# 16_Inputs_Card_schematic.net
KiCad netlist of a schematic drawn in EasyEDA
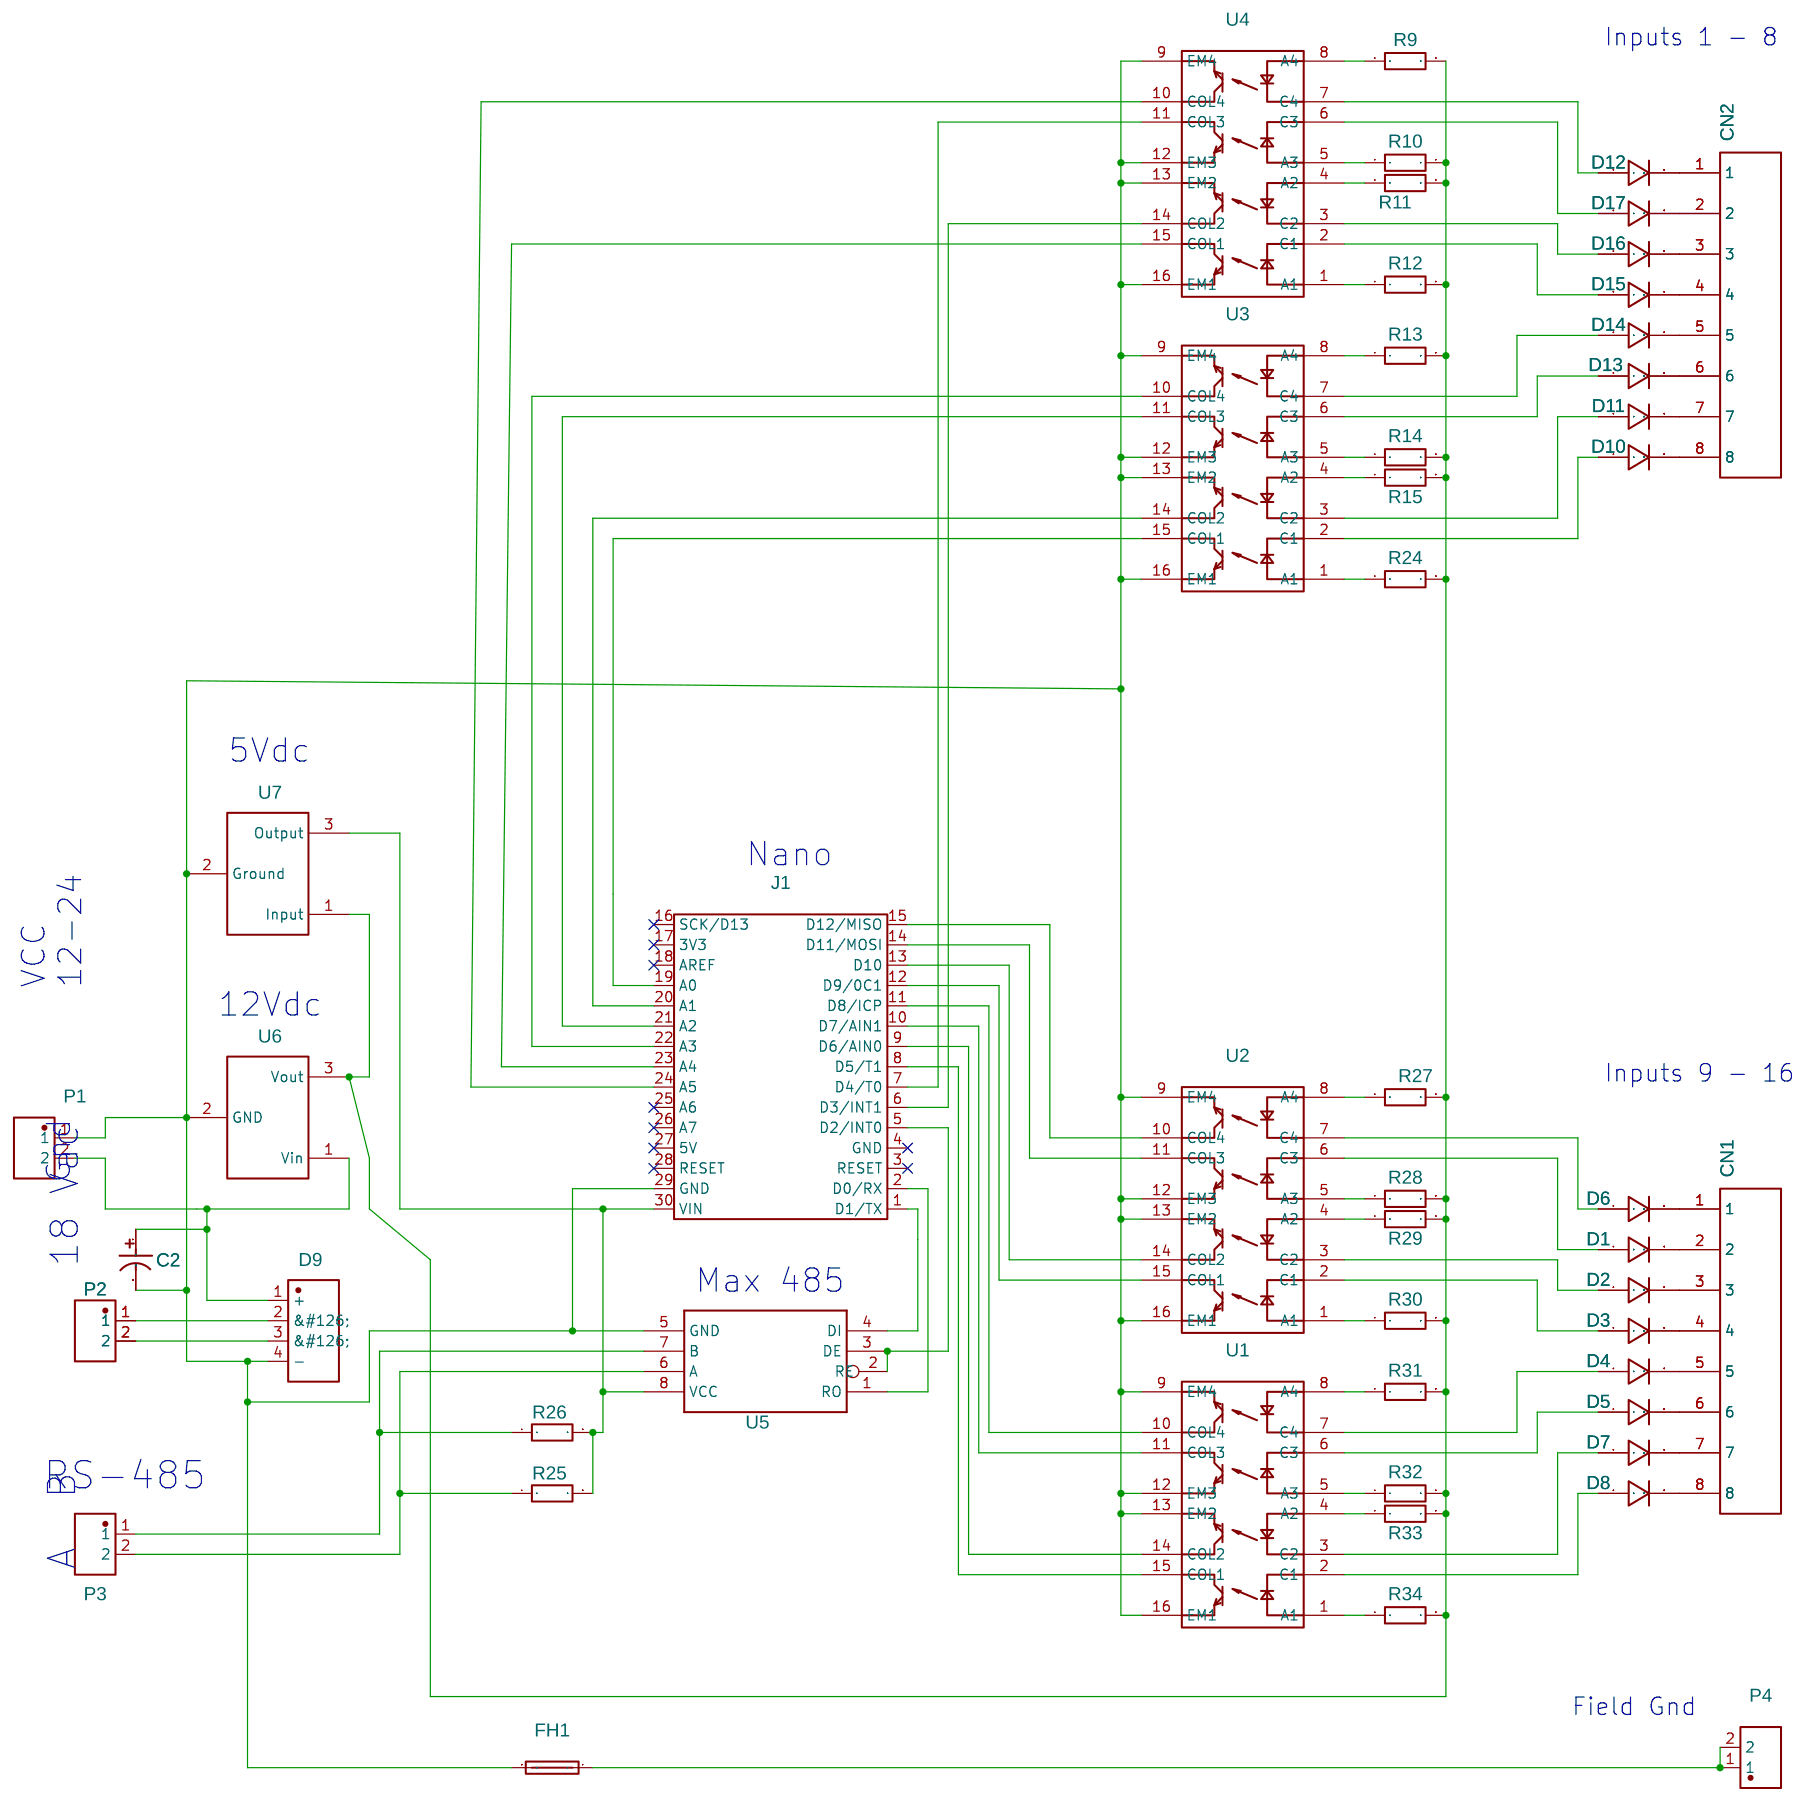
[diagram p0: schematic sheet]

(export (version "E")
  (design (tool "Eeschema 10.0.6"))
  (components
    (comp (ref "C2")
      (value "470uF")
      (fields
        (field (name "BOM_Manufacturer Part") "470uF 100V 16*25")
        (field (name "BOM_Supplier Part") "C72551")
      )
      (libsource (lib "") (part "470uF 100V 16*25"))
    )
    (comp (ref "CN1")
      (value "WJ25C-B-7.62-8P-13-00A")
      (fields (field (name "BOM_Supplier Part") "C49492"))
      (libsource (lib "") (part "Unknown_1070_515"))
    )
    (comp (ref "CN2")
      (value "WJ25C-B-7.62-8P-13-00A")
      (fields (field (name "BOM_Supplier Part") "C49492"))
      (libsource (lib "") (part "Unknown_1070_5"))
    )
    (comp (ref "D1")
      (value "1N4001")
      (fields (field (name "BOM_Supplier Part") "C169150"))
      (libsource (lib "") (part "Unknown_1030_465"))
    )
    (comp (ref "D2")
      (value "1N4001")
      (fields (field (name "BOM_Supplier Part") "C169150"))
      (libsource (lib "") (part "Unknown_1030_485"))
    )
    (comp (ref "D3")
      (value "1N4001")
      (fields (field (name "BOM_Supplier Part") "C169150"))
      (libsource (lib "") (part "Unknown_1030_505"))
    )
    (comp (ref "D4")
      (value "1N4001")
      (fields (field (name "BOM_Supplier Part") "C169150"))
      (libsource (lib "") (part "Unknown_1030_525"))
    )
    (comp (ref "D5")
      (value "1N4001")
      (fields (field (name "BOM_Supplier Part") "C169150"))
      (libsource (lib "") (part "Unknown_1030_545"))
    )
    (comp (ref "D6")
      (value "1N4001")
      (fields (field (name "BOM_Supplier Part") "C169150"))
      (libsource (lib "") (part "Unknown_1030_445"))
    )
    (comp (ref "D7")
      (value "1N4001")
      (fields (field (name "BOM_Supplier Part") "C169150"))
      (libsource (lib "") (part "Unknown_1030_565"))
    )
    (comp (ref "D8")
      (value "1N4001")
      (fields (field (name "BOM_Supplier Part") "C169150"))
      (libsource (lib "") (part "Unknown_1030_585"))
    )
    (comp (ref "D9")
      (value "D50SB100")
      (fields (field (name "BOM_Supplier Part") "C411148"))
      (libsource (lib "") (part "Unknown_370_505"))
    )
    (comp (ref "D10")
      (value "1N4001")
      (fields (field (name "BOM_Supplier Part") "C169150"))
      (libsource (lib "") (part "Unknown_1030_75"))
    )
    (comp (ref "D11")
      (value "1N4001")
      (fields (field (name "BOM_Supplier Part") "C169150"))
      (libsource (lib "") (part "Unknown_1030_55"))
    )
    (comp (ref "D12")
      (value "1N4001")
      (fields (field (name "BOM_Supplier Part") "C169150"))
      (libsource (lib "") (part "Unknown_1030_-65"))
    )
    (comp (ref "D13")
      (value "1N4001")
      (fields (field (name "BOM_Supplier Part") "C169150"))
      (libsource (lib "") (part "Unknown_1030_35"))
    )
    (comp (ref "D14")
      (value "1N4001")
      (fields (field (name "BOM_Supplier Part") "C169150"))
      (libsource (lib "") (part "Unknown_1030_15"))
    )
    (comp (ref "D15")
      (value "1N4001")
      (fields (field (name "BOM_Supplier Part") "C169150"))
      (libsource (lib "") (part "Unknown_1030_-5"))
    )
    (comp (ref "D16")
      (value "1N4001")
      (fields (field (name "BOM_Supplier Part") "C169150"))
      (libsource (lib "") (part "Unknown_1030_-25"))
    )
    (comp (ref "D17")
      (value "1N4001")
      (fields (field (name "BOM_Supplier Part") "C169150"))
      (libsource (lib "") (part "Unknown_1030_-45"))
    )
    (comp (ref "FH1")
      (value "64600001003")
      (fields (field (name "BOM_Supplier Part") "C206887"))
      (libsource (lib "") (part "Unknown_495_720"))
    )
    (comp (ref "J1") (value "Arduino_Nano_Header") (libsource (lib "") (part "Unknown_605_375")))
    (comp (ref "P1")
      (value "WJ25C-B-2P")
      (fields (field (name "BOM_Supplier Part") "C8422"))
      (libsource (lib "") (part "Unknown_240_415"))
    )
    (comp (ref "P2")
      (value "WJ25C-B-2P")
      (fields (field (name "BOM_Supplier Part") "C8422"))
      (libsource (lib "") (part "Unknown_270_505"))
    )
    (comp (ref "P3")
      (value "WJ25C-B-2P")
      (fields (field (name "BOM_Supplier Part") "C8422"))
      (libsource (lib "") (part "Unknown_270_610"))
    )
    (comp (ref "P4")
      (value "WJ25C-B-2P")
      (fields (field (name "BOM_Supplier Part") "C8422"))
      (libsource (lib "") (part "Unknown_1090_715"))
    )
    (comp (ref "R9")
      (value "220")
      (fields
        (field (name "BOM_Manufacturer Part") "CFR0W4J0221A50")
        (field (name "BOM_Supplier Part") "C61289")
      )
      (libsource (lib "") (part "CFR0W4J0221A50"))
    )
    (comp (ref "R10")
      (value "220")
      (fields
        (field (name "BOM_Manufacturer Part") "CFR0W4J0221A50")
        (field (name "BOM_Supplier Part") "C61289")
      )
      (libsource (lib "") (part "CFR0W4J0221A50"))
    )
    (comp (ref "R11")
      (value "220")
      (fields
        (field (name "BOM_Manufacturer Part") "CFR0W4J0221A50")
        (field (name "BOM_Supplier Part") "C61289")
      )
      (libsource (lib "") (part "CFR0W4J0221A50"))
    )
    (comp (ref "R12")
      (value "220")
      (fields
        (field (name "BOM_Manufacturer Part") "CFR0W4J0221A50")
        (field (name "BOM_Supplier Part") "C61289")
      )
      (libsource (lib "") (part "CFR0W4J0221A50"))
    )
    (comp (ref "R13")
      (value "220")
      (fields
        (field (name "BOM_Manufacturer Part") "CFR0W4J0221A50")
        (field (name "BOM_Supplier Part") "C61289")
      )
      (libsource (lib "") (part "CFR0W4J0221A50"))
    )
    (comp (ref "R14")
      (value "220")
      (fields
        (field (name "BOM_Manufacturer Part") "CFR0W4J0221A50")
        (field (name "BOM_Supplier Part") "C61289")
      )
      (libsource (lib "") (part "CFR0W4J0221A50"))
    )
    (comp (ref "R15")
      (value "220")
      (fields
        (field (name "BOM_Manufacturer Part") "CFR0W4J0221A50")
        (field (name "BOM_Supplier Part") "C61289")
      )
      (libsource (lib "") (part "CFR0W4J0221A50"))
    )
    (comp (ref "R24")
      (value "220")
      (fields
        (field (name "BOM_Manufacturer Part") "CFR0W4J0221A50")
        (field (name "BOM_Supplier Part") "C61289")
      )
      (libsource (lib "") (part "CFR0W4J0221A50"))
    )
    (comp (ref "R25")
      (value "10K")
      (fields
        (field (name "BOM_Manufacturer Part") "CFR0W4J0103A50")
        (field (name "BOM_Supplier Part") "C61299")
      )
      (libsource (lib "") (part "CFR0W4J0103A50"))
    )
    (comp (ref "R26")
      (value "10K")
      (fields
        (field (name "BOM_Manufacturer Part") "CFR0W4J0103A50")
        (field (name "BOM_Supplier Part") "C61299")
      )
      (libsource (lib "") (part "CFR0W4J0103A50"))
    )
    (comp (ref "R27")
      (value "220")
      (fields
        (field (name "BOM_Manufacturer Part") "CFR0W4J0221A50")
        (field (name "BOM_Supplier Part") "C61289")
      )
      (libsource (lib "") (part "CFR0W4J0221A50"))
    )
    (comp (ref "R28")
      (value "220")
      (fields
        (field (name "BOM_Manufacturer Part") "CFR0W4J0221A50")
        (field (name "BOM_Supplier Part") "C61289")
      )
      (libsource (lib "") (part "CFR0W4J0221A50"))
    )
    (comp (ref "R29")
      (value "220")
      (fields
        (field (name "BOM_Manufacturer Part") "CFR0W4J0221A50")
        (field (name "BOM_Supplier Part") "C61289")
      )
      (libsource (lib "") (part "CFR0W4J0221A50"))
    )
    (comp (ref "R30")
      (value "220")
      (fields
        (field (name "BOM_Manufacturer Part") "CFR0W4J0221A50")
        (field (name "BOM_Supplier Part") "C61289")
      )
      (libsource (lib "") (part "CFR0W4J0221A50"))
    )
    (comp (ref "R31")
      (value "220")
      (fields
        (field (name "BOM_Manufacturer Part") "CFR0W4J0221A50")
        (field (name "BOM_Supplier Part") "C61289")
      )
      (libsource (lib "") (part "CFR0W4J0221A50"))
    )
    (comp (ref "R32")
      (value "220")
      (fields
        (field (name "BOM_Manufacturer Part") "CFR0W4J0221A50")
        (field (name "BOM_Supplier Part") "C61289")
      )
      (libsource (lib "") (part "CFR0W4J0221A50"))
    )
    (comp (ref "R33")
      (value "220")
      (fields
        (field (name "BOM_Manufacturer Part") "CFR0W4J0221A50")
        (field (name "BOM_Supplier Part") "C61289")
      )
      (libsource (lib "") (part "CFR0W4J0221A50"))
    )
    (comp (ref "R34")
      (value "220")
      (fields
        (field (name "BOM_Manufacturer Part") "CFR0W4J0221A50")
        (field (name "BOM_Supplier Part") "C61289")
      )
      (libsource (lib "") (part "CFR0W4J0221A50"))
    )
    (comp (ref "U1")
      (value "ILQ2")
      (fields (field (name "BOM_Supplier Part") "C145338"))
      (libsource (lib "") (part "ILQ2"))
    )
    (comp (ref "U2")
      (value "ILQ2")
      (fields (field (name "BOM_Supplier Part") "C145338"))
      (libsource (lib "") (part "ILQ2"))
    )
    (comp (ref "U3")
      (value "ILQ2")
      (fields (field (name "BOM_Supplier Part") "C145338"))
      (libsource (lib "") (part "ILQ2"))
    )
    (comp (ref "U4")
      (value "ILQ2")
      (fields (field (name "BOM_Supplier Part") "C145338"))
      (libsource (lib "") (part "ILQ2"))
    )
    (comp (ref "U5") (value "MAX485DIL") (libsource (lib "") (part "Unknown_600_520")))
    (comp (ref "U6")
      (value "CJ7812")
      (fields (field (name "BOM_Supplier Part") "C77894"))
      (libsource (lib "") (part "Unknown_355_400"))
    )
    (comp (ref "U7")
      (value "MC7805BTG")
      (fields (field (name "BOM_Supplier Part") "C45385"))
      (libsource (lib "") (part "Unknown_355_280"))
    )
  )
  (nets
    (net (code "1") (name "Net-(CN1-Pad1)") (class "Default")
      (node (ref "CN1") (pin "1") (pinfunction "1_1") (pintype "input"))
      (node (ref "D6") (pin "2") (pinfunction "2_2") (pintype "unspecified"))
    )
    (net (code "2") (name "Net-(CN1-Pad2)") (class "Default")
      (node (ref "CN1") (pin "2") (pinfunction "2_2") (pintype "input"))
      (node (ref "D1") (pin "2") (pinfunction "2_2") (pintype "unspecified"))
    )
    (net (code "3") (name "Net-(CN1-Pad3)") (class "Default")
      (node (ref "CN1") (pin "3") (pinfunction "3_3") (pintype "input"))
      (node (ref "D2") (pin "2") (pinfunction "2_2") (pintype "unspecified"))
    )
    (net (code "4") (name "Net-(CN1-Pad4)") (class "Default")
      (node (ref "CN1") (pin "4") (pinfunction "4_4") (pintype "input"))
      (node (ref "D3") (pin "2") (pinfunction "2_2") (pintype "unspecified"))
    )
    (net (code "5") (name "Net-(CN1-Pad5)") (class "Default")
      (node (ref "CN1") (pin "5") (pinfunction "5_5") (pintype "input"))
      (node (ref "D4") (pin "2") (pinfunction "2_2") (pintype "unspecified"))
    )
    (net (code "6") (name "Net-(CN1-Pad6)") (class "Default")
      (node (ref "CN1") (pin "6") (pinfunction "6_6") (pintype "input"))
      (node (ref "D5") (pin "2") (pinfunction "2_2") (pintype "unspecified"))
    )
    (net (code "7") (name "Net-(CN1-Pad7)") (class "Default")
      (node (ref "CN1") (pin "7") (pinfunction "7_7") (pintype "input"))
      (node (ref "D7") (pin "2") (pinfunction "2_2") (pintype "unspecified"))
    )
    (net (code "8") (name "Net-(CN1-Pad8)") (class "Default")
      (node (ref "CN1") (pin "8") (pinfunction "8_8") (pintype "input"))
      (node (ref "D8") (pin "2") (pinfunction "2_2") (pintype "unspecified"))
    )
    (net (code "9") (name "Net-(CN2-Pad1)") (class "Default")
      (node (ref "CN2") (pin "1") (pinfunction "1_1") (pintype "input"))
      (node (ref "D12") (pin "2") (pinfunction "2_2") (pintype "unspecified"))
    )
    (net (code "10") (name "Net-(CN2-Pad2)") (class "Default")
      (node (ref "CN2") (pin "2") (pinfunction "2_2") (pintype "input"))
      (node (ref "D17") (pin "2") (pinfunction "2_2") (pintype "unspecified"))
    )
    (net (code "11") (name "Net-(CN2-Pad3)") (class "Default")
      (node (ref "CN2") (pin "3") (pinfunction "3_3") (pintype "input"))
      (node (ref "D16") (pin "2") (pinfunction "2_2") (pintype "unspecified"))
    )
    (net (code "12") (name "Net-(CN2-Pad4)") (class "Default")
      (node (ref "CN2") (pin "4") (pinfunction "4_4") (pintype "input"))
      (node (ref "D15") (pin "2") (pinfunction "2_2") (pintype "unspecified"))
    )
    (net (code "13") (name "Net-(CN2-Pad5)") (class "Default")
      (node (ref "CN2") (pin "5") (pinfunction "5_5") (pintype "input"))
      (node (ref "D14") (pin "2") (pinfunction "2_2") (pintype "unspecified"))
    )
    (net (code "14") (name "Net-(CN2-Pad6)") (class "Default")
      (node (ref "CN2") (pin "6") (pinfunction "6_6") (pintype "input"))
      (node (ref "D13") (pin "2") (pinfunction "2_2") (pintype "unspecified"))
    )
    (net (code "15") (name "Net-(CN2-Pad7)") (class "Default")
      (node (ref "CN2") (pin "7") (pinfunction "7_7") (pintype "input"))
      (node (ref "D11") (pin "2") (pinfunction "2_2") (pintype "unspecified"))
    )
    (net (code "16") (name "Net-(CN2-Pad8)") (class "Default")
      (node (ref "CN2") (pin "8") (pinfunction "8_8") (pintype "input"))
      (node (ref "D10") (pin "2") (pinfunction "2_2") (pintype "unspecified"))
    )
    (net (code "17") (name "Net-(D9-&#126;-Pad2)") (class "Default")
      (node (ref "D9") (pin "2") (pinfunction "&#126;_2") (pintype "unspecified"))
      (node (ref "P2") (pin "1") (pinfunction "1_1") (pintype "unspecified"))
    )
    (net (code "18") (name "Net-(D9-&#126;-Pad3)") (class "Default")
      (node (ref "D9") (pin "3") (pinfunction "&#126;_3") (pintype "unspecified"))
      (node (ref "P2") (pin "2") (pinfunction "2_2") (pintype "unspecified"))
    )
    (net (code "19") (name "Net-(D9-+)") (class "Default")
      (node (ref "C2") (pin "1") (pinfunction "1_1") (pintype "input"))
      (node (ref "D9") (pin "1") (pinfunction "+_1") (pintype "unspecified"))
      (node (ref "P1") (pin "2") (pinfunction "2_2") (pintype "unspecified"))
      (node (ref "U6") (pin "1") (pinfunction "Vin_1") (pintype "unspecified"))
    )
    (net (code "20") (name "Net-(D9--)") (class "Default")
      (node (ref "C2") (pin "2") (pinfunction "2_2") (pintype "input"))
      (node (ref "D9") (pin "4") (pinfunction "-_4") (pintype "unspecified"))
      (node (ref "FH1") (pin "2") (pinfunction "2_2") (pintype "unspecified"))
      (node (ref "J1") (pin "29") (pinfunction "GND_29") (pintype "unspecified"))
      (node (ref "P1") (pin "1") (pinfunction "1_1") (pintype "unspecified"))
      (node (ref "U1") (pin "12") (pinfunction "EM3_12") (pintype "unspecified"))
      (node (ref "U1") (pin "13") (pinfunction "EM2_13") (pintype "unspecified"))
      (node (ref "U1") (pin "16") (pinfunction "EM1_16") (pintype "unspecified"))
      (node (ref "U1") (pin "9") (pinfunction "EM4_9") (pintype "unspecified"))
      (node (ref "U2") (pin "12") (pinfunction "EM3_12") (pintype "unspecified"))
      (node (ref "U2") (pin "13") (pinfunction "EM2_13") (pintype "unspecified"))
      (node (ref "U2") (pin "16") (pinfunction "EM1_16") (pintype "unspecified"))
      (node (ref "U2") (pin "9") (pinfunction "EM4_9") (pintype "unspecified"))
      (node (ref "U3") (pin "12") (pinfunction "EM3_12") (pintype "unspecified"))
      (node (ref "U3") (pin "13") (pinfunction "EM2_13") (pintype "unspecified"))
      (node (ref "U3") (pin "16") (pinfunction "EM1_16") (pintype "unspecified"))
      (node (ref "U3") (pin "9") (pinfunction "EM4_9") (pintype "unspecified"))
      (node (ref "U4") (pin "12") (pinfunction "EM3_12") (pintype "unspecified"))
      (node (ref "U4") (pin "13") (pinfunction "EM2_13") (pintype "unspecified"))
      (node (ref "U4") (pin "16") (pinfunction "EM1_16") (pintype "unspecified"))
      (node (ref "U4") (pin "9") (pinfunction "EM4_9") (pintype "unspecified"))
      (node (ref "U5") (pin "5") (pinfunction "GND_5") (pintype "unspecified"))
      (node (ref "U6") (pin "2") (pinfunction "GND_2") (pintype "unspecified"))
      (node (ref "U7") (pin "2") (pinfunction "Ground_2") (pintype "unspecified"))
    )
    (net (code "21") (name "Net-(FH1-Pad1)") (class "Default")
      (node (ref "FH1") (pin "1") (pinfunction "1_1") (pintype "unspecified"))
      (node (ref "P4") (pin "1") (pinfunction "1_1") (pintype "unspecified"))
      (node (ref "P4") (pin "2") (pinfunction "2_2") (pintype "unspecified"))
    )
    (net (code "22") (name "Net-(J1-A0)") (class "Default")
      (node (ref "J1") (pin "19") (pinfunction "A0_19") (pintype "unspecified"))
      (node (ref "U3") (pin "15") (pinfunction "COL1_15") (pintype "unspecified"))
    )
    (net (code "23") (name "Net-(J1-A1)") (class "Default")
      (node (ref "J1") (pin "20") (pinfunction "A1_20") (pintype "unspecified"))
      (node (ref "U3") (pin "14") (pinfunction "COL2_14") (pintype "unspecified"))
    )
    (net (code "24") (name "Net-(J1-A2)") (class "Default")
      (node (ref "J1") (pin "21") (pinfunction "A2_21") (pintype "unspecified"))
      (node (ref "U3") (pin "11") (pinfunction "COL3_11") (pintype "unspecified"))
    )
    (net (code "25") (name "Net-(J1-A3)") (class "Default")
      (node (ref "J1") (pin "22") (pinfunction "A3_22") (pintype "unspecified"))
      (node (ref "U3") (pin "10") (pinfunction "COL4_10") (pintype "unspecified"))
    )
    (net (code "26") (name "Net-(J1-A4)") (class "Default")
      (node (ref "J1") (pin "23") (pinfunction "A4_23") (pintype "unspecified"))
      (node (ref "U4") (pin "15") (pinfunction "COL1_15") (pintype "unspecified"))
    )
    (net (code "27") (name "Net-(J1-A5)") (class "Default")
      (node (ref "J1") (pin "24") (pinfunction "A5_24") (pintype "unspecified"))
      (node (ref "U4") (pin "10") (pinfunction "COL4_10") (pintype "unspecified"))
    )
    (net (code "28") (name "Net-(J1-D0{slash}RX)") (class "Default")
      (node (ref "J1") (pin "2") (pinfunction "D0/RX_2") (pintype "unspecified"))
      (node (ref "U5") (pin "1") (pinfunction "RO_1") (pintype "unspecified"))
    )
    (net (code "29") (name "Net-(J1-D1{slash}TX)") (class "Default")
      (node (ref "J1") (pin "1") (pinfunction "D1/TX_1") (pintype "unspecified"))
      (node (ref "U5") (pin "4") (pinfunction "DI_4") (pintype "unspecified"))
    )
    (net (code "30") (name "Net-(J1-D2{slash}INT0)") (class "Default")
      (node (ref "J1") (pin "5") (pinfunction "D2/INT0_5") (pintype "unspecified"))
      (node (ref "U5") (pin "2") (pinfunction "RE_2") (pintype "unspecified"))
      (node (ref "U5") (pin "3") (pinfunction "DE_3") (pintype "unspecified"))
    )
    (net (code "31") (name "Net-(J1-D3{slash}INT1)") (class "Default")
      (node (ref "J1") (pin "6") (pinfunction "D3/INT1_6") (pintype "unspecified"))
      (node (ref "U4") (pin "14") (pinfunction "COL2_14") (pintype "unspecified"))
    )
    (net (code "32") (name "Net-(J1-D4{slash}T0)") (class "Default")
      (node (ref "J1") (pin "7") (pinfunction "D4/T0_7") (pintype "unspecified"))
      (node (ref "U4") (pin "11") (pinfunction "COL3_11") (pintype "unspecified"))
    )
    (net (code "33") (name "Net-(J1-D5{slash}T1)") (class "Default")
      (node (ref "J1") (pin "8") (pinfunction "D5/T1_8") (pintype "unspecified"))
      (node (ref "U1") (pin "15") (pinfunction "COL1_15") (pintype "unspecified"))
    )
    (net (code "34") (name "Net-(J1-D6{slash}AIN0)") (class "Default")
      (node (ref "J1") (pin "9") (pinfunction "D6/AIN0_9") (pintype "unspecified"))
      (node (ref "U1") (pin "14") (pinfunction "COL2_14") (pintype "unspecified"))
    )
    (net (code "35") (name "Net-(J1-D7{slash}AIN1)") (class "Default")
      (node (ref "J1") (pin "10") (pinfunction "D7/AIN1_10") (pintype "unspecified"))
      (node (ref "U1") (pin "11") (pinfunction "COL3_11") (pintype "unspecified"))
    )
    (net (code "36") (name "Net-(J1-D8{slash}ICP)") (class "Default")
      (node (ref "J1") (pin "11") (pinfunction "D8/ICP_11") (pintype "unspecified"))
      (node (ref "U1") (pin "10") (pinfunction "COL4_10") (pintype "unspecified"))
    )
    (net (code "37") (name "Net-(J1-D9{slash}0C1)") (class "Default")
      (node (ref "J1") (pin "12") (pinfunction "D9/0C1_12") (pintype "unspecified"))
      (node (ref "U2") (pin "15") (pinfunction "COL1_15") (pintype "unspecified"))
    )
    (net (code "38") (name "Net-(J1-D10)") (class "Default")
      (node (ref "J1") (pin "13") (pinfunction "D10_13") (pintype "unspecified"))
      (node (ref "U2") (pin "14") (pinfunction "COL2_14") (pintype "unspecified"))
    )
    (net (code "39") (name "Net-(J1-D11{slash}MOSI)") (class "Default")
      (node (ref "J1") (pin "14") (pinfunction "D11/MOSI_14") (pintype "unspecified"))
      (node (ref "U2") (pin "11") (pinfunction "COL3_11") (pintype "unspecified"))
    )
    (net (code "40") (name "Net-(J1-D12{slash}MISO)") (class "Default")
      (node (ref "J1") (pin "15") (pinfunction "D12/MISO_15") (pintype "unspecified"))
      (node (ref "U2") (pin "10") (pinfunction "COL4_10") (pintype "unspecified"))
    )
    (net (code "41") (name "Net-(J1-VIN)") (class "Default")
      (node (ref "J1") (pin "30") (pinfunction "VIN_30") (pintype "unspecified"))
      (node (ref "R25") (pin "2") (pinfunction "2_2") (pintype "input"))
      (node (ref "R26") (pin "2") (pinfunction "2_2") (pintype "input"))
      (node (ref "U5") (pin "8") (pinfunction "VCC_8") (pintype "unspecified"))
      (node (ref "U7") (pin "3") (pinfunction "Output_3") (pintype "unspecified"))
    )
    (net (code "42") (name "Net-(U1-A1)") (class "Default")
      (node (ref "R34") (pin "1") (pinfunction "1_1") (pintype "input"))
      (node (ref "U1") (pin "1") (pinfunction "A1_1") (pintype "unspecified"))
    )
    (net (code "43") (name "Net-(U1-A2)") (class "Default")
      (node (ref "R33") (pin "1") (pinfunction "1_1") (pintype "input"))
      (node (ref "U1") (pin "4") (pinfunction "A2_4") (pintype "unspecified"))
    )
    (net (code "44") (name "Net-(U1-A3)") (class "Default")
      (node (ref "R32") (pin "1") (pinfunction "1_1") (pintype "input"))
      (node (ref "U1") (pin "5") (pinfunction "A3_5") (pintype "unspecified"))
    )
    (net (code "45") (name "Net-(U1-A4)") (class "Default")
      (node (ref "R31") (pin "1") (pinfunction "1_1") (pintype "input"))
      (node (ref "U1") (pin "8") (pinfunction "A4_8") (pintype "unspecified"))
    )
    (net (code "46") (name "Net-(U1-C1)") (class "Default")
      (node (ref "D8") (pin "1") (pinfunction "1_1") (pintype "unspecified"))
      (node (ref "U1") (pin "2") (pinfunction "C1_2") (pintype "unspecified"))
    )
    (net (code "47") (name "Net-(U1-C2)") (class "Default")
      (node (ref "D7") (pin "1") (pinfunction "1_1") (pintype "unspecified"))
      (node (ref "U1") (pin "3") (pinfunction "C2_3") (pintype "unspecified"))
    )
    (net (code "48") (name "Net-(U1-C3)") (class "Default")
      (node (ref "D5") (pin "1") (pinfunction "1_1") (pintype "unspecified"))
      (node (ref "U1") (pin "6") (pinfunction "C3_6") (pintype "unspecified"))
    )
    (net (code "49") (name "Net-(U1-C4)") (class "Default")
      (node (ref "D4") (pin "1") (pinfunction "1_1") (pintype "unspecified"))
      (node (ref "U1") (pin "7") (pinfunction "C4_7") (pintype "unspecified"))
    )
    (net (code "50") (name "Net-(U2-A1)") (class "Default")
      (node (ref "R30") (pin "1") (pinfunction "1_1") (pintype "input"))
      (node (ref "U2") (pin "1") (pinfunction "A1_1") (pintype "unspecified"))
    )
    (net (code "51") (name "Net-(U2-A2)") (class "Default")
      (node (ref "R29") (pin "1") (pinfunction "1_1") (pintype "input"))
      (node (ref "U2") (pin "4") (pinfunction "A2_4") (pintype "unspecified"))
    )
    (net (code "52") (name "Net-(U2-A3)") (class "Default")
      (node (ref "R28") (pin "1") (pinfunction "1_1") (pintype "input"))
      (node (ref "U2") (pin "5") (pinfunction "A3_5") (pintype "unspecified"))
    )
    (net (code "53") (name "Net-(U2-A4)") (class "Default")
      (node (ref "R27") (pin "1") (pinfunction "1_1") (pintype "input"))
      (node (ref "U2") (pin "8") (pinfunction "A4_8") (pintype "unspecified"))
    )
    (net (code "54") (name "Net-(U2-C1)") (class "Default")
      (node (ref "D3") (pin "1") (pinfunction "1_1") (pintype "unspecified"))
      (node (ref "U2") (pin "2") (pinfunction "C1_2") (pintype "unspecified"))
    )
    (net (code "55") (name "Net-(U2-C2)") (class "Default")
      (node (ref "D2") (pin "1") (pinfunction "1_1") (pintype "unspecified"))
      (node (ref "U2") (pin "3") (pinfunction "C2_3") (pintype "unspecified"))
    )
    (net (code "56") (name "Net-(U2-C3)") (class "Default")
      (node (ref "D1") (pin "1") (pinfunction "1_1") (pintype "unspecified"))
      (node (ref "U2") (pin "6") (pinfunction "C3_6") (pintype "unspecified"))
    )
    (net (code "57") (name "Net-(U2-C4)") (class "Default")
      (node (ref "D6") (pin "1") (pinfunction "1_1") (pintype "unspecified"))
      (node (ref "U2") (pin "7") (pinfunction "C4_7") (pintype "unspecified"))
    )
    (net (code "58") (name "Net-(U3-A1)") (class "Default")
      (node (ref "R24") (pin "1") (pinfunction "1_1") (pintype "input"))
      (node (ref "U3") (pin "1") (pinfunction "A1_1") (pintype "unspecified"))
    )
    (net (code "59") (name "Net-(U3-A2)") (class "Default")
      (node (ref "R15") (pin "1") (pinfunction "1_1") (pintype "input"))
      (node (ref "U3") (pin "4") (pinfunction "A2_4") (pintype "unspecified"))
    )
    (net (code "60") (name "Net-(U3-A3)") (class "Default")
      (node (ref "R14") (pin "1") (pinfunction "1_1") (pintype "input"))
      (node (ref "U3") (pin "5") (pinfunction "A3_5") (pintype "unspecified"))
    )
    (net (code "61") (name "Net-(U3-A4)") (class "Default")
      (node (ref "R13") (pin "1") (pinfunction "1_1") (pintype "input"))
      (node (ref "U3") (pin "8") (pinfunction "A4_8") (pintype "unspecified"))
    )
    (net (code "62") (name "Net-(U3-C1)") (class "Default")
      (node (ref "D10") (pin "1") (pinfunction "1_1") (pintype "unspecified"))
      (node (ref "U3") (pin "2") (pinfunction "C1_2") (pintype "unspecified"))
    )
    (net (code "63") (name "Net-(U3-C2)") (class "Default")
      (node (ref "D11") (pin "1") (pinfunction "1_1") (pintype "unspecified"))
      (node (ref "U3") (pin "3") (pinfunction "C2_3") (pintype "unspecified"))
    )
    (net (code "64") (name "Net-(U3-C3)") (class "Default")
      (node (ref "D13") (pin "1") (pinfunction "1_1") (pintype "unspecified"))
      (node (ref "U3") (pin "6") (pinfunction "C3_6") (pintype "unspecified"))
    )
    (net (code "65") (name "Net-(U3-C4)") (class "Default")
      (node (ref "D14") (pin "1") (pinfunction "1_1") (pintype "unspecified"))
      (node (ref "U3") (pin "7") (pinfunction "C4_7") (pintype "unspecified"))
    )
    (net (code "66") (name "Net-(U4-A1)") (class "Default")
      (node (ref "R12") (pin "1") (pinfunction "1_1") (pintype "input"))
      (node (ref "U4") (pin "1") (pinfunction "A1_1") (pintype "unspecified"))
    )
    (net (code "67") (name "Net-(U4-A2)") (class "Default")
      (node (ref "R11") (pin "1") (pinfunction "1_1") (pintype "input"))
      (node (ref "U4") (pin "4") (pinfunction "A2_4") (pintype "unspecified"))
    )
    (net (code "68") (name "Net-(U4-A3)") (class "Default")
      (node (ref "R10") (pin "1") (pinfunction "1_1") (pintype "input"))
      (node (ref "U4") (pin "5") (pinfunction "A3_5") (pintype "unspecified"))
    )
    (net (code "69") (name "Net-(U4-A4)") (class "Default")
      (node (ref "R9") (pin "1") (pinfunction "1_1") (pintype "input"))
      (node (ref "U4") (pin "8") (pinfunction "A4_8") (pintype "unspecified"))
    )
    (net (code "70") (name "Net-(U4-C1)") (class "Default")
      (node (ref "D15") (pin "1") (pinfunction "1_1") (pintype "unspecified"))
      (node (ref "U4") (pin "2") (pinfunction "C1_2") (pintype "unspecified"))
    )
    (net (code "71") (name "Net-(U4-C2)") (class "Default")
      (node (ref "D16") (pin "1") (pinfunction "1_1") (pintype "unspecified"))
      (node (ref "U4") (pin "3") (pinfunction "C2_3") (pintype "unspecified"))
    )
    (net (code "72") (name "Net-(U4-C3)") (class "Default")
      (node (ref "D17") (pin "1") (pinfunction "1_1") (pintype "unspecified"))
      (node (ref "U4") (pin "6") (pinfunction "C3_6") (pintype "unspecified"))
    )
    (net (code "73") (name "Net-(U4-C4)") (class "Default")
      (node (ref "D12") (pin "1") (pinfunction "1_1") (pintype "unspecified"))
      (node (ref "U4") (pin "7") (pinfunction "C4_7") (pintype "unspecified"))
    )
    (net (code "74") (name "Net-(U5-A)") (class "Default")
      (node (ref "P3") (pin "2") (pinfunction "2_2") (pintype "unspecified"))
      (node (ref "R25") (pin "1") (pinfunction "1_1") (pintype "input"))
      (node (ref "U5") (pin "6") (pinfunction "A_6") (pintype "unspecified"))
    )
    (net (code "75") (name "Net-(U5-B)") (class "Default")
      (node (ref "P3") (pin "1") (pinfunction "1_1") (pintype "unspecified"))
      (node (ref "R26") (pin "1") (pinfunction "1_1") (pintype "input"))
      (node (ref "U5") (pin "7") (pinfunction "B_7") (pintype "unspecified"))
    )
    (net (code "76") (name "Net-(U6-Vout)") (class "Default")
      (node (ref "R10") (pin "2") (pinfunction "2_2") (pintype "input"))
      (node (ref "R11") (pin "2") (pinfunction "2_2") (pintype "input"))
      (node (ref "R12") (pin "2") (pinfunction "2_2") (pintype "input"))
      (node (ref "R13") (pin "2") (pinfunction "2_2") (pintype "input"))
      (node (ref "R14") (pin "2") (pinfunction "2_2") (pintype "input"))
      (node (ref "R15") (pin "2") (pinfunction "2_2") (pintype "input"))
      (node (ref "R24") (pin "2") (pinfunction "2_2") (pintype "input"))
      (node (ref "R27") (pin "2") (pinfunction "2_2") (pintype "input"))
      (node (ref "R28") (pin "2") (pinfunction "2_2") (pintype "input"))
      (node (ref "R29") (pin "2") (pinfunction "2_2") (pintype "input"))
      (node (ref "R30") (pin "2") (pinfunction "2_2") (pintype "input"))
      (node (ref "R31") (pin "2") (pinfunction "2_2") (pintype "input"))
      (node (ref "R32") (pin "2") (pinfunction "2_2") (pintype "input"))
      (node (ref "R33") (pin "2") (pinfunction "2_2") (pintype "input"))
      (node (ref "R34") (pin "2") (pinfunction "2_2") (pintype "input"))
      (node (ref "R9") (pin "2") (pinfunction "2_2") (pintype "input"))
      (node (ref "U6") (pin "3") (pinfunction "Vout_3") (pintype "unspecified"))
      (node (ref "U7") (pin "1") (pinfunction "Input_1") (pintype "unspecified"))
    )
    (net (code "77") (name "unconnected-(J1-3V3-Pad17)") (class "Default")
      (node (ref "J1") (pin "17") (pinfunction "3V3_17") (pintype "unspecified+no_connect"))
    )
    (net (code "78") (name "unconnected-(J1-5V-Pad27)") (class "Default")
      (node (ref "J1") (pin "27") (pinfunction "5V_27") (pintype "unspecified+no_connect"))
    )
    (net (code "79") (name "unconnected-(J1-A6-Pad25)") (class "Default")
      (node (ref "J1") (pin "25") (pinfunction "A6_25") (pintype "unspecified+no_connect"))
    )
    (net (code "80") (name "unconnected-(J1-A7-Pad26)") (class "Default")
      (node (ref "J1") (pin "26") (pinfunction "A7_26") (pintype "unspecified+no_connect"))
    )
    (net (code "81") (name "unconnected-(J1-AREF-Pad18)") (class "Default")
      (node (ref "J1") (pin "18") (pinfunction "AREF_18") (pintype "unspecified+no_connect"))
    )
    (net (code "82") (name "unconnected-(J1-GND-Pad4)") (class "Default")
      (node (ref "J1") (pin "4") (pinfunction "GND_4") (pintype "unspecified+no_connect"))
    )
    (net (code "83") (name "unconnected-(J1-RESET-Pad3)") (class "Default")
      (node (ref "J1") (pin "3") (pinfunction "RESET_3") (pintype "unspecified+no_connect"))
    )
    (net (code "84") (name "unconnected-(J1-RESET-Pad28)") (class "Default")
      (node (ref "J1") (pin "28") (pinfunction "RESET_28") (pintype "unspecified+no_connect"))
    )
    (net (code "85") (name "unconnected-(J1-SCK{slash}D13-Pad16)") (class "Default")
      (node (ref "J1") (pin "16") (pinfunction "SCK/D13_16") (pintype "unspecified+no_connect"))
    )
  )
)
